# ColinsBlinkySchematic.net
KiCad netlist of a schematic drawn in EAGLE
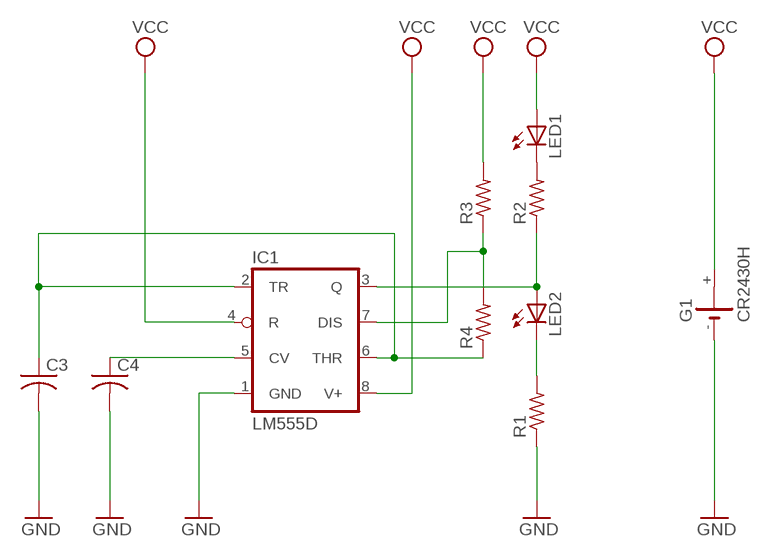
[diagram p0: schematic, sheet 1]

(export (version "E")
  (design (tool "Eeschema 10.0.6"))
  (components
    (comp (ref "C3")
      (value "C-USC0805")
      (footprint "eagle-import:C0805")
      (libsource (lib "eagle-import") (part "C-USC0805"))
    )
    (comp (ref "C4")
      (value "C-USC0805")
      (footprint "eagle-import:C0805")
      (libsource (lib "eagle-import") (part "C-USC0805"))
    )
    (comp (ref "G1")
      (value "CR2430H")
      (footprint "eagle-import:CR2430H")
      (libsource (lib "eagle-import") (part "CR2430H"))
    )
    (comp (ref "IC1")
      (value "LM555D")
      (footprint "eagle-import:SO08")
      (libsource (lib "eagle-import") (part "555DLM"))
    )
    (comp (ref "LED1")
      (value "LED5MM")
      (footprint "eagle-import:LED5MM")
      (libsource (lib "eagle-import") (part "LED5MM"))
    )
    (comp (ref "LED2")
      (value "LED5MM")
      (footprint "eagle-import:LED5MM")
      (libsource (lib "eagle-import") (part "LED5MM"))
    )
    (comp (ref "R1")
      (value "R-US_R0805")
      (footprint "eagle-import:R0805")
      (libsource (lib "eagle-import") (part "R-US_R0805"))
    )
    (comp (ref "R2")
      (value "R-US_R0805")
      (footprint "eagle-import:R0805")
      (libsource (lib "eagle-import") (part "R-US_R0805"))
    )
    (comp (ref "R3")
      (value "R-US_R0805")
      (footprint "eagle-import:R0805")
      (libsource (lib "eagle-import") (part "R-US_R0805"))
    )
    (comp (ref "R4")
      (value "R-US_R0805")
      (footprint "eagle-import:R0805")
      (libsource (lib "eagle-import") (part "R-US_R0805"))
    )
  )
  (nets
    (net (code "1") (name "GND") (class "Default")
      (node (ref "C3") (pin "2") (pinfunction "2_2") (pintype "passive"))
      (node (ref "C4") (pin "2") (pinfunction "2_2") (pintype "passive"))
      (node (ref "G1") (pin "-") (pinfunction "-_-") (pintype "passive"))
      (node (ref "IC1") (pin "1") (pinfunction "GND_1") (pintype "power_in"))
      (node (ref "R1") (pin "1") (pinfunction "1_1") (pintype "passive"))
    )
    (net (code "2") (name "Net-(IC1-CV)") (class "Default")
      (node (ref "C4") (pin "1") (pinfunction "1_1") (pintype "passive"))
      (node (ref "IC1") (pin "5") (pinfunction "CV_5") (pintype "input"))
    )
    (net (code "3") (name "Net-(IC1-DIS)") (class "Default")
      (node (ref "IC1") (pin "7") (pinfunction "DIS_7") (pintype "input"))
      (node (ref "R3") (pin "1") (pinfunction "1_1") (pintype "passive"))
      (node (ref "R4") (pin "2") (pinfunction "2_2") (pintype "passive"))
    )
    (net (code "4") (name "Net-(IC1-Q)") (class "Default")
      (node (ref "IC1") (pin "3") (pinfunction "Q_3") (pintype "output"))
      (node (ref "LED2") (pin "A") (pinfunction "A_A") (pintype "passive"))
      (node (ref "R2") (pin "1") (pinfunction "1_1") (pintype "passive"))
    )
    (net (code "5") (name "Net-(IC1-THR)") (class "Default")
      (node (ref "C3") (pin "1") (pinfunction "1_1") (pintype "passive"))
      (node (ref "IC1") (pin "2") (pinfunction "TR_2") (pintype "input"))
      (node (ref "IC1") (pin "6") (pinfunction "THR_6") (pintype "input"))
      (node (ref "R4") (pin "1") (pinfunction "1_1") (pintype "passive"))
    )
    (net (code "6") (name "Net-(LED1-C)") (class "Default")
      (node (ref "LED1") (pin "K") (pinfunction "C_K") (pintype "passive"))
      (node (ref "R2") (pin "2") (pinfunction "2_2") (pintype "passive"))
    )
    (net (code "7") (name "Net-(LED2-C)") (class "Default")
      (node (ref "LED2") (pin "K") (pinfunction "C_K") (pintype "passive"))
      (node (ref "R1") (pin "2") (pinfunction "2_2") (pintype "passive"))
    )
    (net (code "8") (name "VCC") (class "Default")
      (node (ref "G1") (pin "+") (pinfunction "+_+") (pintype "passive"))
      (node (ref "IC1") (pin "4") (pinfunction "R_4") (pintype "input"))
      (node (ref "IC1") (pin "8") (pinfunction "V+_8") (pintype "power_in"))
      (node (ref "LED1") (pin "A") (pinfunction "A_A") (pintype "passive"))
      (node (ref "R3") (pin "2") (pinfunction "2_2") (pintype "passive"))
    )
    (net (code "9") (name "unconnected-(G1-+-Pad+@1)") (class "Default")
      (node (ref "G1") (pin "+@1") (pinfunction "+_+@1") (pintype "passive"))
    )
  )
)
